# Humidity.net
KiCad netlist of a schematic drawn in EAGLE
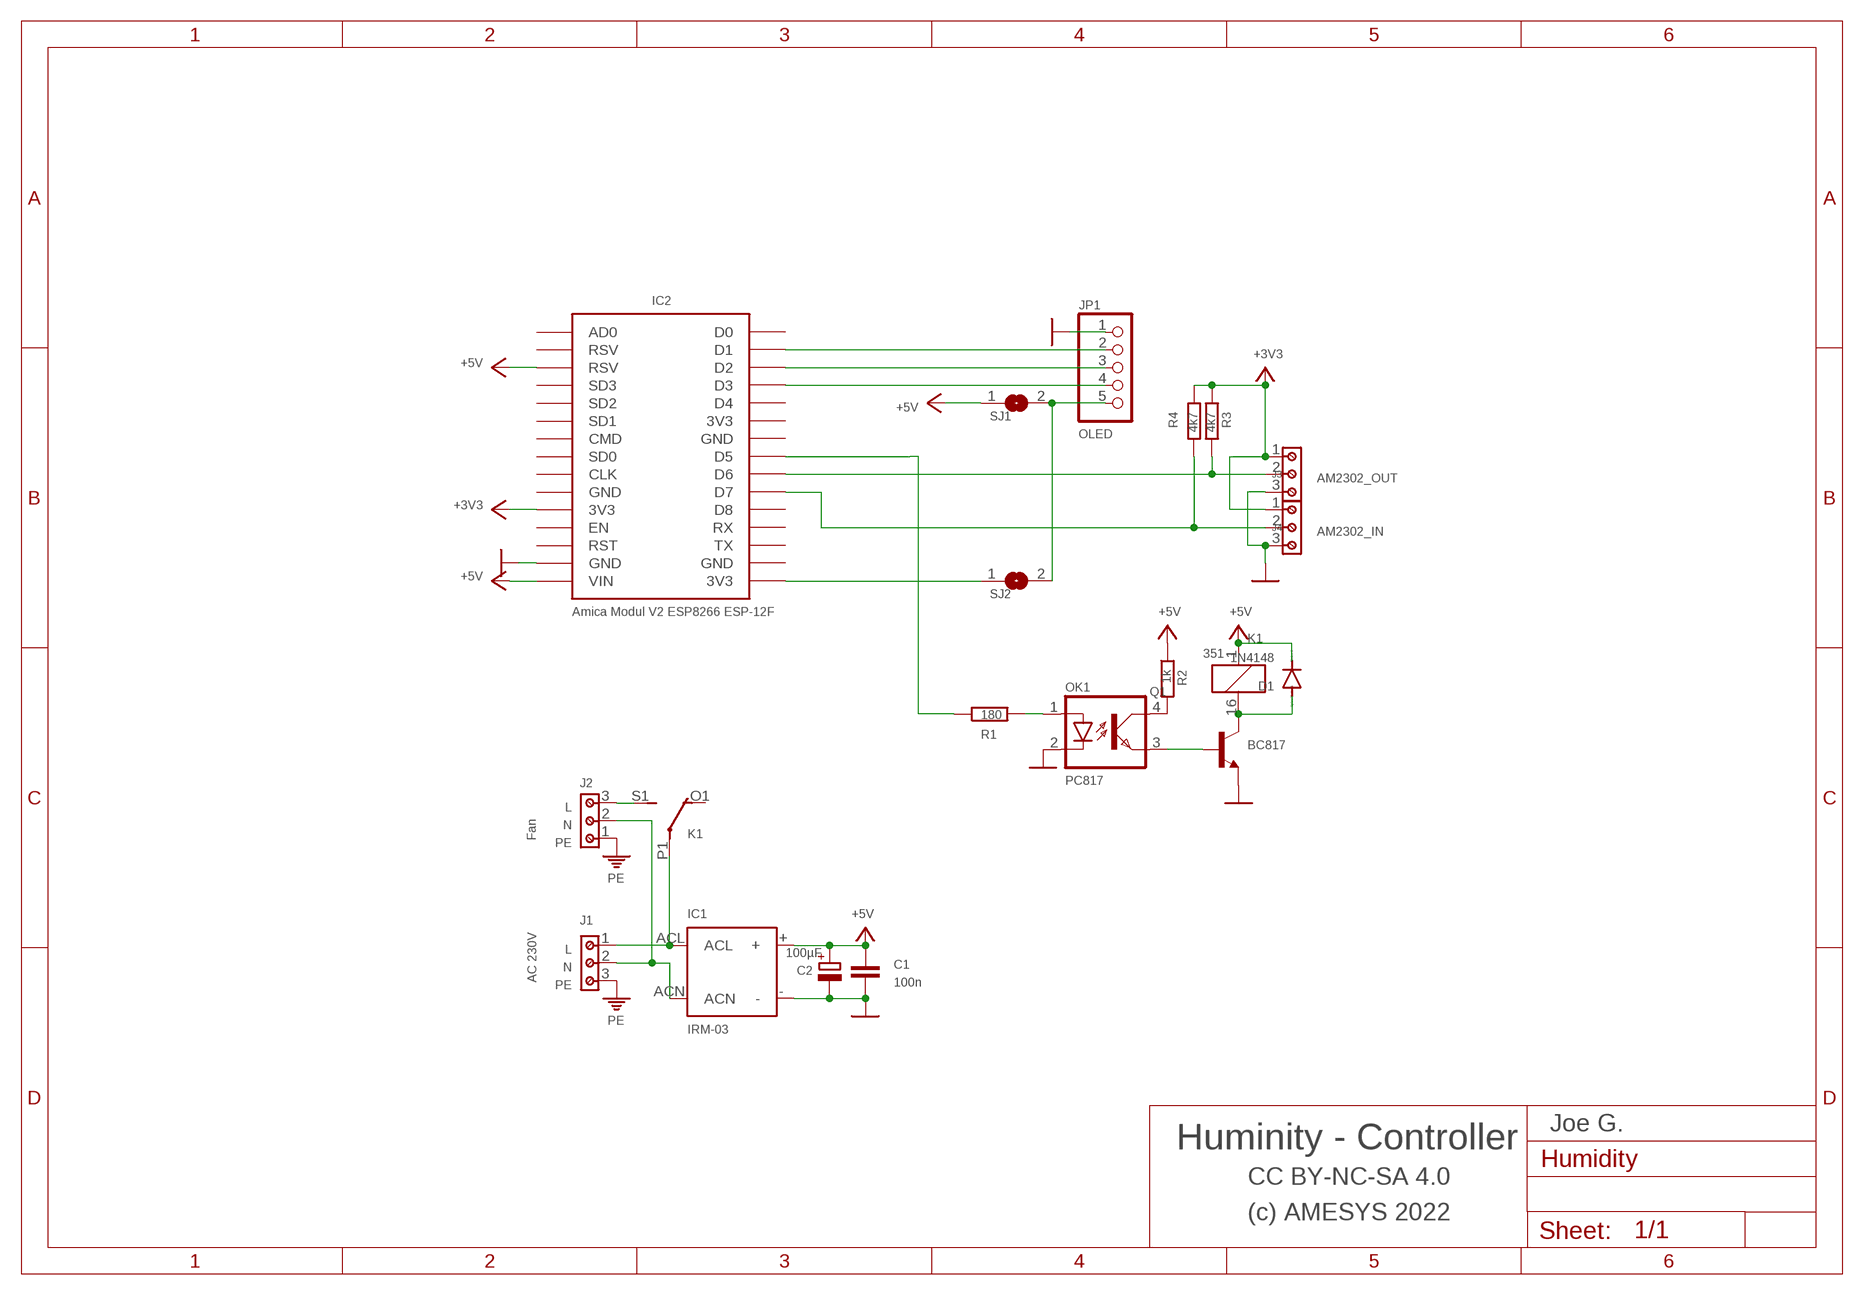
[diagram p0: schematic, sheet 1]

(export (version "E")
  (design (tool "Eeschema 10.0.6"))
  (components
    (comp (ref "C1")
      (value "100n")
      (footprint "eagle-import:C1206")
      (libsource (lib "eagle-import") (part "C-EUC1206"))
    )
    (comp (ref "C2")
      (value "100µF")
      (footprint "eagle-import:SMC_C")
      (libsource (lib "eagle-import") (part "CPOL-EUSMCC"))
    )
    (comp (ref "D1")
      (value "1N4148")
      (footprint "eagle-import:SOD123")
      (libsource (lib "eagle-import") (part "DIODE-SOD123"))
    )
    (comp (ref "IC1")
      (value "IRM-03")
      (footprint "eagle-import:IRM-03")
      (libsource (lib "eagle-import") (part "IRM-03"))
    )
    (comp (ref "IC2")
      (value "Amica Modul V2 ESP8266 ESP-12F")
      (footprint "eagle-import:ESP12E_DEVKIT")
      (libsource (lib "eagle-import") (part "ESP12E_DEVKIT"))
    )
    (comp (ref "J1")
      (value "AC 230V")
      (footprint "eagle-import:691216910003")
      (libsource (lib "eagle-import") (part "691216910003"))
    )
    (comp (ref "J2")
      (value "Fan")
      (footprint "eagle-import:691216910003")
      (libsource (lib "eagle-import") (part "691216910003"))
    )
    (comp (ref "J3")
      (value "AM2302_OUT")
      (footprint "eagle-import:691216710003")
      (libsource (lib "eagle-import") (part "691216710003"))
    )
    (comp (ref "J4")
      (value "AM2302_IN")
      (footprint "eagle-import:691216710003")
      (libsource (lib "eagle-import") (part "691216710003"))
    )
    (comp (ref "JP1")
      (value "OLED")
      (footprint "eagle-import:1X05")
      (libsource (lib "eagle-import") (part "PINHD-1X5"))
    )
    (comp (ref "K1")
      (value "351")
      (footprint "eagle-import:351")
      (libsource (lib "eagle-import") (part "351"))
    )
    (comp (ref "OK1")
      (value "PC817")
      (footprint "eagle-import:DIL04")
      (fields (field (name "MPN") "PC817X4J000F"))
      (libsource (lib "eagle-import") (part "PC817"))
    )
    (comp (ref "Q1")
      (value "BC817")
      (footprint "eagle-import:TRANSISTOR-NPN_SOT23-BEC")
      (libsource (lib "eagle-import") (part "TRANSISTOR-NPN_BC817SMD"))
    )
    (comp (ref "R1")
      (value "180")
      (footprint "eagle-import:R1206")
      (libsource (lib "eagle-import") (part "R-EU_R1206"))
    )
    (comp (ref "R2")
      (value "1k")
      (footprint "eagle-import:M1206")
      (libsource (lib "eagle-import") (part "R-EU_M1206"))
    )
    (comp (ref "R3")
      (value "4k7")
      (footprint "eagle-import:M1206")
      (libsource (lib "eagle-import") (part "R-EU_M1206"))
    )
    (comp (ref "R4")
      (value "4k7")
      (footprint "eagle-import:M1206")
      (libsource (lib "eagle-import") (part "R-EU_M1206"))
    )
    (comp (ref "SJ1") (value "SJ") (footprint "eagle-import:SJ") (libsource (lib "eagle-import") (part "SJ")))
    (comp (ref "SJ2") (value "SJ") (footprint "eagle-import:SJ") (libsource (lib "eagle-import") (part "SJ")))
  )
  (nets
    (net (code "1") (name "+3V3") (class "Default")
      (node (ref "IC2") (pin "3V3@0") (pinfunction "3V3_3V3@0") (pintype "bidirectional"))
      (node (ref "J3") (pin "1") (pinfunction "1_1") (pintype "passive"))
      (node (ref "J4") (pin "1") (pinfunction "1_1") (pintype "passive"))
      (node (ref "R3") (pin "1") (pinfunction "1_1") (pintype "passive"))
      (node (ref "R4") (pin "1") (pinfunction "1_1") (pintype "passive"))
    )
    (net (code "2") (name "+5V") (class "Default")
      (node (ref "C1") (pin "1") (pinfunction "1_1") (pintype "passive"))
      (node (ref "C2") (pin "+") (pinfunction "+_+") (pintype "passive"))
      (node (ref "D1") (pin "C") (pinfunction "C_C") (pintype "passive"))
      (node (ref "IC1") (pin "+") (pinfunction "+_+") (pintype "output"))
      (node (ref "IC2") (pin "RSV@1") (pinfunction "RSV_RSV@1") (pintype "bidirectional"))
      (node (ref "IC2") (pin "VIN") (pinfunction "VIN_VIN") (pintype "bidirectional"))
      (node (ref "K1") (pin "1") (pinfunction "1_1") (pintype "passive"))
      (node (ref "R2") (pin "1") (pinfunction "1_1") (pintype "passive"))
      (node (ref "SJ1") (pin "1") (pinfunction "1_1") (pintype "passive"))
    )
    (net (code "3") (name "GND") (class "Default")
      (node (ref "C1") (pin "2") (pinfunction "2_2") (pintype "passive"))
      (node (ref "C2") (pin "-") (pinfunction "-_-") (pintype "passive"))
      (node (ref "IC1") (pin "-") (pinfunction "-_-") (pintype "output"))
      (node (ref "IC2") (pin "GND@1") (pinfunction "GND_GND@1") (pintype "bidirectional"))
      (node (ref "J3") (pin "3") (pinfunction "3_3") (pintype "passive"))
      (node (ref "J4") (pin "3") (pinfunction "3_3") (pintype "passive"))
      (node (ref "JP1") (pin "1") (pinfunction "1_1") (pintype "passive"))
      (node (ref "OK1") (pin "2") (pinfunction "C_2") (pintype "passive"))
      (node (ref "Q1") (pin "E") (pinfunction "E_E") (pintype "passive"))
    )
    (net (code "4") (name "Net-(IC1-PadACN)") (class "Default")
      (node (ref "IC1") (pin "ACN") (pinfunction "ACN_ACN") (pintype "input"))
      (node (ref "J1") (pin "2") (pinfunction "2_2") (pintype "passive"))
      (node (ref "J2") (pin "2") (pinfunction "2_2") (pintype "passive"))
    )
    (net (code "5") (name "Net-(IC2-3V3-Pad3V3@2)") (class "Default")
      (node (ref "IC2") (pin "3V3@2") (pinfunction "3V3_3V3@2") (pintype "bidirectional"))
      (node (ref "SJ2") (pin "1") (pinfunction "1_1") (pintype "passive"))
    )
    (net (code "6") (name "Net-(IC2-PadD1)") (class "Default")
      (node (ref "IC2") (pin "D1") (pinfunction "D1_D1") (pintype "bidirectional"))
      (node (ref "JP1") (pin "2") (pinfunction "2_2") (pintype "passive"))
    )
    (net (code "7") (name "Net-(IC2-PadD2)") (class "Default")
      (node (ref "IC2") (pin "D2") (pinfunction "D2_D2") (pintype "bidirectional"))
      (node (ref "JP1") (pin "3") (pinfunction "3_3") (pintype "passive"))
    )
    (net (code "8") (name "Net-(IC2-PadD3)") (class "Default")
      (node (ref "IC2") (pin "D3") (pinfunction "D3_D3") (pintype "bidirectional"))
      (node (ref "JP1") (pin "4") (pinfunction "4_4") (pintype "passive"))
    )
    (net (code "9") (name "Net-(IC2-PadD5)") (class "Default")
      (node (ref "IC2") (pin "D5") (pinfunction "D5_D5") (pintype "bidirectional"))
      (node (ref "R1") (pin "1") (pinfunction "1_1") (pintype "passive"))
    )
    (net (code "10") (name "Net-(IC2-PadD6)") (class "Default")
      (node (ref "IC2") (pin "D6") (pinfunction "D6_D6") (pintype "bidirectional"))
      (node (ref "J3") (pin "2") (pinfunction "2_2") (pintype "passive"))
      (node (ref "R3") (pin "2") (pinfunction "2_2") (pintype "passive"))
    )
    (net (code "11") (name "Net-(IC2-PadD7)") (class "Default")
      (node (ref "IC2") (pin "D7") (pinfunction "D7_D7") (pintype "bidirectional"))
      (node (ref "J4") (pin "2") (pinfunction "2_2") (pintype "passive"))
      (node (ref "R4") (pin "2") (pinfunction "2_2") (pintype "passive"))
    )
    (net (code "12") (name "Net-(JP1-Pad5)") (class "Default")
      (node (ref "JP1") (pin "5") (pinfunction "5_5") (pintype "passive"))
      (node (ref "SJ1") (pin "2") (pinfunction "2_2") (pintype "passive"))
      (node (ref "SJ2") (pin "2") (pinfunction "2_2") (pintype "passive"))
    )
    (net (code "13") (name "Net-(K1A-2)") (class "Default")
      (node (ref "D1") (pin "A") (pinfunction "A_A") (pintype "passive"))
      (node (ref "K1") (pin "16") (pinfunction "2_16") (pintype "passive"))
      (node (ref "Q1") (pin "C") (pinfunction "C_C") (pintype "passive"))
    )
    (net (code "14") (name "Net-(K1B-P)") (class "Default")
      (node (ref "IC1") (pin "ACL") (pinfunction "ACL_ACL") (pintype "input"))
      (node (ref "J1") (pin "1") (pinfunction "1_1") (pintype "passive"))
      (node (ref "K1") (pin "P1") (pinfunction "P_P1") (pintype "passive"))
    )
    (net (code "15") (name "Net-(K1B-S)") (class "Default")
      (node (ref "J2") (pin "3") (pinfunction "3_3") (pintype "passive"))
      (node (ref "K1") (pin "S1") (pinfunction "S_S1") (pintype "passive"))
    )
    (net (code "16") (name "Net-(OK1-A)") (class "Default")
      (node (ref "OK1") (pin "1") (pinfunction "A_1") (pintype "passive"))
      (node (ref "R1") (pin "2") (pinfunction "2_2") (pintype "passive"))
    )
    (net (code "17") (name "Net-(OK1-COL)") (class "Default")
      (node (ref "OK1") (pin "4") (pinfunction "COL_4") (pintype "passive"))
      (node (ref "R2") (pin "2") (pinfunction "2_2") (pintype "passive"))
    )
    (net (code "18") (name "Net-(OK1-EMIT)") (class "Default")
      (node (ref "OK1") (pin "3") (pinfunction "EMIT_3") (pintype "passive"))
      (node (ref "Q1") (pin "B") (pinfunction "B_B") (pintype "passive"))
    )
    (net (code "19") (name "PE") (class "Default")
      (node (ref "J1") (pin "3") (pinfunction "3_3") (pintype "passive"))
      (node (ref "J2") (pin "1") (pinfunction "1_1") (pintype "passive"))
    )
    (net (code "20") (name "unconnected-(IC2-3V3-Pad3V3@1)") (class "Default")
      (node (ref "IC2") (pin "3V3@1") (pinfunction "3V3_3V3@1") (pintype "bidirectional"))
    )
    (net (code "21") (name "unconnected-(IC2-GND-PadGND@0)") (class "Default")
      (node (ref "IC2") (pin "GND@0") (pinfunction "GND_GND@0") (pintype "bidirectional"))
    )
    (net (code "22") (name "unconnected-(IC2-GND-PadGND@2)") (class "Default")
      (node (ref "IC2") (pin "GND@2") (pinfunction "GND_GND@2") (pintype "bidirectional"))
    )
    (net (code "23") (name "unconnected-(IC2-GND-PadGND@3)") (class "Default")
      (node (ref "IC2") (pin "GND@3") (pinfunction "GND_GND@3") (pintype "bidirectional"))
    )
    (net (code "24") (name "unconnected-(IC2-PadAD0)") (class "Default")
      (node (ref "IC2") (pin "AD0") (pinfunction "AD0_AD0") (pintype "bidirectional"))
    )
    (net (code "25") (name "unconnected-(IC2-PadCLK)") (class "Default")
      (node (ref "IC2") (pin "CLK") (pinfunction "CLK_CLK") (pintype "bidirectional"))
    )
    (net (code "26") (name "unconnected-(IC2-PadCMD)") (class "Default")
      (node (ref "IC2") (pin "CMD") (pinfunction "CMD_CMD") (pintype "bidirectional"))
    )
    (net (code "27") (name "unconnected-(IC2-PadD0)") (class "Default")
      (node (ref "IC2") (pin "D0") (pinfunction "D0_D0") (pintype "bidirectional"))
    )
    (net (code "28") (name "unconnected-(IC2-PadD4)") (class "Default")
      (node (ref "IC2") (pin "D4") (pinfunction "D4_D4") (pintype "bidirectional"))
    )
    (net (code "29") (name "unconnected-(IC2-PadD8)") (class "Default")
      (node (ref "IC2") (pin "D8") (pinfunction "D8_D8") (pintype "bidirectional"))
    )
    (net (code "30") (name "unconnected-(IC2-PadEN)") (class "Default")
      (node (ref "IC2") (pin "EN") (pinfunction "EN_EN") (pintype "bidirectional"))
    )
    (net (code "31") (name "unconnected-(IC2-PadRST)") (class "Default")
      (node (ref "IC2") (pin "RST") (pinfunction "RST_RST") (pintype "bidirectional"))
    )
    (net (code "32") (name "unconnected-(IC2-PadRX)") (class "Default")
      (node (ref "IC2") (pin "RX") (pinfunction "RX_RX") (pintype "bidirectional"))
    )
    (net (code "33") (name "unconnected-(IC2-PadSD0)") (class "Default")
      (node (ref "IC2") (pin "SD0") (pinfunction "SD0_SD0") (pintype "bidirectional"))
    )
    (net (code "34") (name "unconnected-(IC2-PadSD1)") (class "Default")
      (node (ref "IC2") (pin "SD1") (pinfunction "SD1_SD1") (pintype "bidirectional"))
    )
    (net (code "35") (name "unconnected-(IC2-PadSD2)") (class "Default")
      (node (ref "IC2") (pin "SD2") (pinfunction "SD2_SD2") (pintype "bidirectional"))
    )
    (net (code "36") (name "unconnected-(IC2-PadSD3)") (class "Default")
      (node (ref "IC2") (pin "SD3") (pinfunction "SD3_SD3") (pintype "bidirectional"))
    )
    (net (code "37") (name "unconnected-(IC2-PadTX)") (class "Default")
      (node (ref "IC2") (pin "TX") (pinfunction "TX_TX") (pintype "bidirectional"))
    )
    (net (code "38") (name "unconnected-(IC2-RSV-PadRSV@0)") (class "Default")
      (node (ref "IC2") (pin "RSV@0") (pinfunction "RSV_RSV@0") (pintype "bidirectional"))
    )
    (net (code "39") (name "unconnected-(K1B-O-PadO1)") (class "Default")
      (node (ref "K1") (pin "O1") (pinfunction "O_O1") (pintype "passive"))
    )
  )
)
